# STM32.net
KiCad netlist of a schematic drawn in Altium Designer
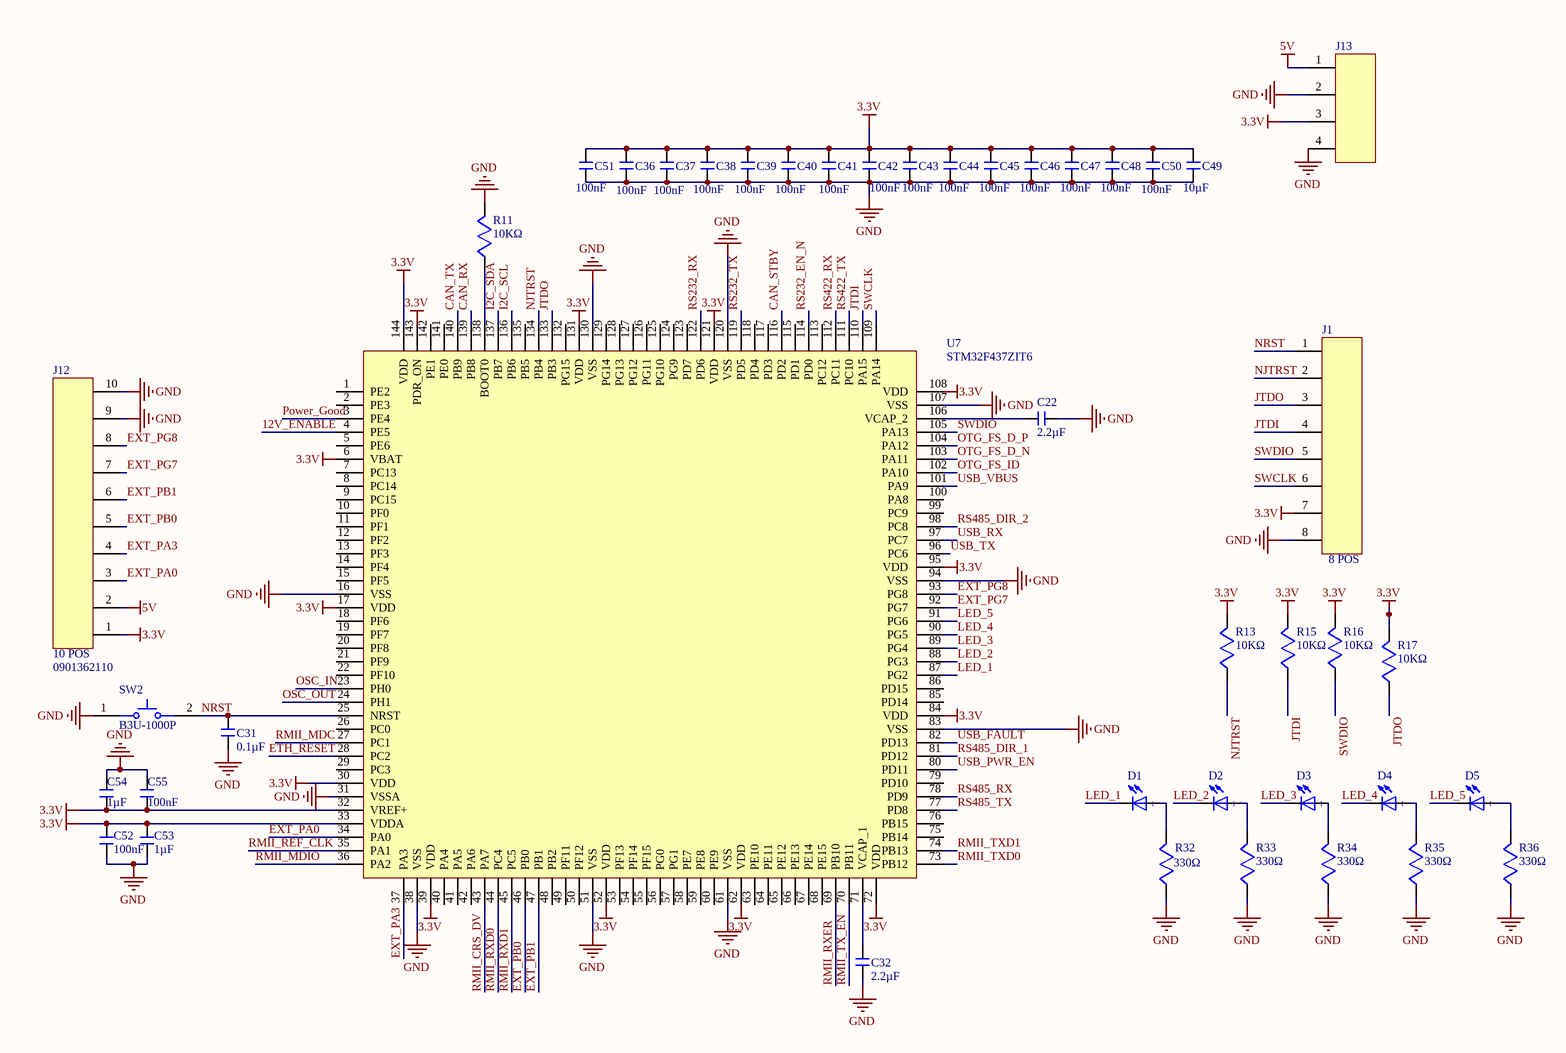
[diagram p0: STM32.SchDoc]

(export (version "E")
  (design (tool "Eeschema 10.0.6"))
  (components
    (comp (ref "C22")
      (value "2.2µF")
      (footprint "402 capacitor - duplicate")
      (description "CAP SMD 402")
      (fields (field (name "MPN") "C1005X5R1V225K050BC") (field (name "Comment") "0402 capacitor"))
      (libsource (lib "Schlib1") (part "CAP SMD 402"))
    )
    (comp (ref "C31")
      (value "0.1µF")
      (footprint "402 capacitor - duplicate")
      (description "CAP SMD 402")
      (fields (field (name "MPN") "CL05A104KA5NNNC") (field (name "Comment") "0402 capacitor"))
      (libsource (lib "Schlib1") (part "CAP SMD 402"))
    )
    (comp (ref "C32")
      (value "2.2µF")
      (footprint "402 capacitor - duplicate")
      (description "CAP SMD 402")
      (fields (field (name "MPN") "C1005X5R1V225K050BC") (field (name "Comment") "0402 capacitor"))
      (libsource (lib "Schlib1") (part "CAP SMD 402"))
    )
    (comp (ref "C36")
      (value "100nF")
      (footprint "402 capacitor - duplicate")
      (description "CAP SMD 402")
      (fields (field (name "MPN") "CL05A104KA5NNNC") (field (name "Comment") "0402 capacitor"))
      (libsource (lib "Schlib1") (part "CAP SMD 402"))
    )
    (comp (ref "C37")
      (value "100nF")
      (footprint "402 capacitor - duplicate")
      (description "CAP SMD 402")
      (fields (field (name "MPN") "CL05A104KA5NNNC") (field (name "Comment") "0402 capacitor"))
      (libsource (lib "Schlib1") (part "CAP SMD 402"))
    )
    (comp (ref "C38")
      (value "100nF")
      (footprint "402 capacitor - duplicate")
      (description "CAP SMD 402")
      (fields (field (name "MPN") "CL05A104KA5NNNC") (field (name "Comment") "0402 capacitor"))
      (libsource (lib "Schlib1") (part "CAP SMD 402"))
    )
    (comp (ref "C39")
      (value "100nF")
      (footprint "402 capacitor - duplicate")
      (description "CAP SMD 402")
      (fields (field (name "MPN") "CL05A104KA5NNNC") (field (name "Comment") "0402 capacitor"))
      (libsource (lib "Schlib1") (part "CAP SMD 402"))
    )
    (comp (ref "C40")
      (value "100nF")
      (footprint "402 capacitor - duplicate")
      (description "CAP SMD 402")
      (fields (field (name "MPN") "CL05A104KA5NNNC") (field (name "Comment") "0402 capacitor"))
      (libsource (lib "Schlib1") (part "CAP SMD 402"))
    )
    (comp (ref "C41")
      (value "100nF")
      (footprint "402 capacitor - duplicate")
      (description "CAP SMD 402")
      (fields (field (name "MPN") "CL05A104KA5NNNC") (field (name "Comment") "0402 capacitor"))
      (libsource (lib "Schlib1") (part "CAP SMD 402"))
    )
    (comp (ref "C42")
      (value "100nF")
      (footprint "402 capacitor - duplicate")
      (description "CAP SMD 402")
      (fields (field (name "MPN") "CL05A104KA5NNNC") (field (name "Comment") "0402 capacitor"))
      (libsource (lib "Schlib1") (part "CAP SMD 402"))
    )
    (comp (ref "C43")
      (value "100nF")
      (footprint "402 capacitor - duplicate")
      (description "CAP SMD 402")
      (fields (field (name "MPN") "CL05A104KA5NNNC") (field (name "Comment") "0402 capacitor"))
      (libsource (lib "Schlib1") (part "CAP SMD 402"))
    )
    (comp (ref "C44")
      (value "100nF")
      (footprint "402 capacitor - duplicate")
      (description "CAP SMD 402")
      (fields (field (name "MPN") "CL05A104KA5NNNC") (field (name "Comment") "0402 capacitor"))
      (libsource (lib "Schlib1") (part "CAP SMD 402"))
    )
    (comp (ref "C45")
      (value "100nF")
      (footprint "402 capacitor - duplicate")
      (description "CAP SMD 402")
      (fields (field (name "MPN") "CL05A104KA5NNNC") (field (name "Comment") "0402 capacitor"))
      (libsource (lib "Schlib1") (part "CAP SMD 402"))
    )
    (comp (ref "C46")
      (value "100nF")
      (footprint "402 capacitor - duplicate")
      (description "CAP SMD 402")
      (fields (field (name "MPN") "CL05A104KA5NNNC") (field (name "Comment") "0402 capacitor"))
      (libsource (lib "Schlib1") (part "CAP SMD 402"))
    )
    (comp (ref "C47")
      (value "100nF")
      (footprint "402 capacitor - duplicate")
      (description "CAP SMD 402")
      (fields (field (name "MPN") "CL05A104KA5NNNC") (field (name "Comment") "0402 capacitor"))
      (libsource (lib "Schlib1") (part "CAP SMD 402"))
    )
    (comp (ref "C48")
      (value "100nF")
      (footprint "402 capacitor - duplicate")
      (description "CAP SMD 402")
      (fields (field (name "MPN") "CL05A104KA5NNNC") (field (name "Comment") "0402 capacitor"))
      (libsource (lib "Schlib1") (part "CAP SMD 402"))
    )
    (comp (ref "C49")
      (value "10µF")
      (footprint "603 CAPACITOR")
      (description "CAP SMD 0603")
      (fields (field (name "MPN") "GRM188R61E106MA73D") (field (name "Comment") "0603 CAPACİTOR"))
      (libsource (lib "Schlib1") (part "CAP SMD 0603"))
    )
    (comp (ref "C50")
      (value "100nF")
      (footprint "402 capacitor - duplicate")
      (description "CAP SMD 402")
      (fields (field (name "MPN") "CL05A104KA5NNNC") (field (name "Comment") "0402 capacitor"))
      (libsource (lib "Schlib1") (part "CAP SMD 402"))
    )
    (comp (ref "C51")
      (value "100nF")
      (footprint "402 capacitor - duplicate")
      (description "CAP SMD 402")
      (fields (field (name "MPN") "CL05A104KA5NNNC") (field (name "Comment") "0402 capacitor"))
      (libsource (lib "Schlib1") (part "CAP SMD 402"))
    )
    (comp (ref "C52")
      (value "100nF")
      (footprint "402 capacitor - duplicate")
      (description "CAP SMD 402")
      (fields (field (name "MPN") "CL05A104KA5NNNC") (field (name "Comment") "0402 capacitor"))
      (libsource (lib "Schlib1") (part "CAP SMD 402"))
    )
    (comp (ref "C53")
      (value "1µF")
      (footprint "402 capacitor - duplicate")
      (description "CAP SMD 402")
      (fields (field (name "MPN") "GRM155R6YA105KE11D") (field (name "Comment") "0402 capacitor"))
      (libsource (lib "Schlib1") (part "CAP SMD 402"))
    )
    (comp (ref "C54")
      (value "1µF")
      (footprint "402 capacitor - duplicate")
      (description "CAP SMD 402")
      (fields (field (name "MPN") "GRM155R6YA105KE11D") (field (name "Comment") "0402 capacitor"))
      (libsource (lib "Schlib1") (part "CAP SMD 402"))
    )
    (comp (ref "C55")
      (value "100nF")
      (footprint "402 capacitor - duplicate")
      (description "CAP SMD 402")
      (fields (field (name "MPN") "CL05A104KA5NNNC") (field (name "Comment") "0402 capacitor"))
      (libsource (lib "Schlib1") (part "CAP SMD 402"))
    )
    (comp (ref "D1")
      (value "150060RS75000")
      (footprint "150080GS75000")
      (description "LED RED CLEAR 0603 SMD")
      (libsource (lib "Schlib1") (part "150060RS75000"))
    )
    (comp (ref "D2")
      (value "150060RS75000")
      (footprint "150080GS75000")
      (description "LED RED CLEAR 0603 SMD")
      (libsource (lib "Schlib1") (part "150060RS75000"))
    )
    (comp (ref "D3")
      (value "150060RS75000")
      (footprint "150080GS75000")
      (description "LED RED CLEAR 0603 SMD")
      (libsource (lib "Schlib1") (part "150060RS75000"))
    )
    (comp (ref "D4")
      (value "150060RS75000")
      (footprint "150080GS75000")
      (description "LED RED CLEAR 0603 SMD")
      (libsource (lib "Schlib1") (part "150060RS75000"))
    )
    (comp (ref "D5")
      (value "150060RS75000")
      (footprint "150080GS75000")
      (description "LED RED CLEAR 0603 SMD")
      (libsource (lib "Schlib1") (part "150060RS75000"))
    )
    (comp (ref "J1")
      (value "8 POS")
      (footprint "0901362108")
      (description "CONN HEADER R/A 8POS 2.54MM")
      (fields (field (name "MPN") "0901362108"))
      (libsource (lib "Schlib1") (part "0901362108"))
    )
    (comp (ref "J12")
      (value "10 POS")
      (footprint "0901362110")
      (description "CONN HEADER R/A 10POS 2.54MM")
      (fields (field (name "MPN") "0901362110"))
      (libsource (lib "Schlib1") (part "0901362110"))
    )
    (comp (ref "J13")
      (value "61300411821")
      (footprint "61300411821")
      (description "WR-PHD 2.54 MM SOCKET HEADER 4 P")
      (libsource (lib "Schlib1") (part "61300411821"))
    )
    (comp (ref "R11")
      (value "10KΩ")
      (footprint "402 RESISTOR")
      (description "RES SMD 0402")
      (fields (field (name "MPN") "RNCF0402BTE10K0") (field (name "Comment") "0402. RESİSTOR"))
      (libsource (lib "Schlib1") (part "RES SMD 0402"))
    )
    (comp (ref "R13")
      (value "10KΩ")
      (footprint "402 RESISTOR")
      (description "RES SMD 0402")
      (fields (field (name "MPN") "RNCF0402BTE10K0") (field (name "Comment") "0402. RESİSTOR"))
      (libsource (lib "Schlib1") (part "RES SMD 0402"))
    )
    (comp (ref "R15")
      (value "10KΩ")
      (footprint "402 RESISTOR")
      (description "RES SMD 0402")
      (fields (field (name "MPN") "RNCF0402BTE10K0") (field (name "Comment") "0402. RESİSTOR"))
      (libsource (lib "Schlib1") (part "RES SMD 0402"))
    )
    (comp (ref "R16")
      (value "10KΩ")
      (footprint "402 RESISTOR")
      (description "RES SMD 0402")
      (fields (field (name "MPN") "RNCF0402BTE10K0") (field (name "Comment") "0402. RESİSTOR"))
      (libsource (lib "Schlib1") (part "RES SMD 0402"))
    )
    (comp (ref "R17")
      (value "10KΩ")
      (footprint "402 RESISTOR")
      (description "RES SMD 0402")
      (fields (field (name "MPN") "RNCF0402BTE10K0") (field (name "Comment") "0402. RESİSTOR"))
      (libsource (lib "Schlib1") (part "RES SMD 0402"))
    )
    (comp (ref "R32")
      (value "330Ω")
      (footprint "402 RESISTOR")
      (description "RES SMD 0402")
      (fields (field (name "MPN") "RC0402FR-13300RL") (field (name "Comment") "0402. RESİSTOR"))
      (libsource (lib "Schlib1") (part "RES SMD 0402"))
    )
    (comp (ref "R33")
      (value "330Ω")
      (footprint "402 RESISTOR")
      (description "RES SMD 0402")
      (fields (field (name "MPN") "RC0402FR-13300RL") (field (name "Comment") "0402. RESİSTOR"))
      (libsource (lib "Schlib1") (part "RES SMD 0402"))
    )
    (comp (ref "R34")
      (value "330Ω")
      (footprint "402 RESISTOR")
      (description "RES SMD 0402")
      (fields (field (name "MPN") "RC0402FR-13300RL") (field (name "Comment") "0402. RESİSTOR"))
      (libsource (lib "Schlib1") (part "RES SMD 0402"))
    )
    (comp (ref "R35")
      (value "330Ω")
      (footprint "402 RESISTOR")
      (description "RES SMD 0402")
      (fields (field (name "MPN") "RC0402FR-13300RL") (field (name "Comment") "0402. RESİSTOR"))
      (libsource (lib "Schlib1") (part "RES SMD 0402"))
    )
    (comp (ref "R36")
      (value "330Ω")
      (footprint "402 RESISTOR")
      (description "RES SMD 0402")
      (fields (field (name "MPN") "RC0402FR-13300RL") (field (name "Comment") "0402. RESİSTOR"))
      (libsource (lib "Schlib1") (part "RES SMD 0402"))
    )
    (comp (ref "SW2")
      (value "B3U-1000P")
      (footprint "OMRON-B3U-1000_V")
      (description "Tactile Switch, SPST-NO, 0.05 A, 12 V, -25 to 70 degC, 2-Pin SMD, RoHS, Tape and Reel")
      (libsource (lib "Veysel Can Tosun") (part "SW-SPST-NO-2"))
    )
    (comp (ref "U7")
      (value "STM32F437ZIT6")
      (footprint "STM32F437ZIT6")
      (fields (field (name "MANUFACTURER") "STMicroelectronics"))
      (libsource (lib "Schlib1") (part "STM32F437ZIT6"))
    )
  )
  (nets
    (net (code "1") (name "/12V_ENABLE") (class "Default")
      (node (ref "U7") (pin "4") (pinfunction "PE5_4") (pintype "passive"))
    )
    (net (code "2") (name "/CAN_RX") (class "Default")
      (node (ref "U7") (pin "139") (pinfunction "PB8_139") (pintype "passive"))
    )
    (net (code "3") (name "/CAN_STBY") (class "Default")
      (node (ref "U7") (pin "116") (pinfunction "PD2_116") (pintype "passive"))
    )
    (net (code "4") (name "/CAN_TX") (class "Default")
      (node (ref "U7") (pin "140") (pinfunction "PB9_140") (pintype "passive"))
    )
    (net (code "5") (name "/ETH_RESET") (class "Default")
      (node (ref "U7") (pin "28") (pinfunction "PC2_28") (pintype "passive"))
    )
    (net (code "6") (name "/EXT_PA0") (class "Default")
      (node (ref "J12") (pin "3") (pintype "passive"))
      (node (ref "U7") (pin "34") (pinfunction "PA0_34") (pintype "passive"))
    )
    (net (code "7") (name "/EXT_PA3") (class "Default")
      (node (ref "J12") (pin "4") (pintype "passive"))
      (node (ref "U7") (pin "37") (pinfunction "PA3_37") (pintype "passive"))
    )
    (net (code "8") (name "/EXT_PB0") (class "Default")
      (node (ref "J12") (pin "5") (pintype "passive"))
      (node (ref "U7") (pin "46") (pinfunction "PB0_46") (pintype "passive"))
    )
    (net (code "9") (name "/EXT_PB1") (class "Default")
      (node (ref "J12") (pin "6") (pintype "passive"))
      (node (ref "U7") (pin "47") (pinfunction "PB1_47") (pintype "passive"))
    )
    (net (code "10") (name "/EXT_PG7") (class "Default")
      (node (ref "J12") (pin "7") (pintype "passive"))
      (node (ref "U7") (pin "92") (pinfunction "PG7_92") (pintype "passive"))
    )
    (net (code "11") (name "/EXT_PG8") (class "Default")
      (node (ref "J12") (pin "8") (pintype "passive"))
      (node (ref "U7") (pin "93") (pinfunction "PG8_93") (pintype "passive"))
    )
    (net (code "12") (name "/I2C_SCL") (class "Default")
      (node (ref "U7") (pin "136") (pinfunction "PB6_136") (pintype "passive"))
    )
    (net (code "13") (name "/I2C_SDA") (class "Default")
      (node (ref "U7") (pin "137") (pinfunction "PB7_137") (pintype "passive"))
    )
    (net (code "14") (name "/JTDI") (class "Default")
      (node (ref "J1") (pin "4") (pintype "passive"))
      (node (ref "R15") (pin "1") (pintype "passive"))
      (node (ref "U7") (pin "110") (pinfunction "PA15_110") (pintype "passive"))
    )
    (net (code "15") (name "/JTDO") (class "Default")
      (node (ref "J1") (pin "3") (pintype "passive"))
      (node (ref "R17") (pin "1") (pintype "passive"))
      (node (ref "U7") (pin "133") (pinfunction "PB3_133") (pintype "passive"))
    )
    (net (code "16") (name "/LED_1") (class "Default")
      (node (ref "D1") (pin "1") (pinfunction "NEG_1") (pintype "passive"))
      (node (ref "U7") (pin "87") (pinfunction "PG2_87") (pintype "passive"))
    )
    (net (code "17") (name "/LED_2") (class "Default")
      (node (ref "D2") (pin "1") (pinfunction "NEG_1") (pintype "passive"))
      (node (ref "U7") (pin "88") (pinfunction "PG3_88") (pintype "passive"))
    )
    (net (code "18") (name "/LED_3") (class "Default")
      (node (ref "D3") (pin "1") (pinfunction "NEG_1") (pintype "passive"))
      (node (ref "U7") (pin "89") (pinfunction "PG4_89") (pintype "passive"))
    )
    (net (code "19") (name "/LED_4") (class "Default")
      (node (ref "D4") (pin "1") (pinfunction "NEG_1") (pintype "passive"))
      (node (ref "U7") (pin "90") (pinfunction "PG5_90") (pintype "passive"))
    )
    (net (code "20") (name "/LED_5") (class "Default")
      (node (ref "D5") (pin "1") (pinfunction "NEG_1") (pintype "passive"))
      (node (ref "U7") (pin "91") (pinfunction "PG6_91") (pintype "passive"))
    )
    (net (code "21") (name "/NJTRST") (class "Default")
      (node (ref "J1") (pin "2") (pintype "passive"))
      (node (ref "R13") (pin "1") (pintype "passive"))
      (node (ref "U7") (pin "134") (pinfunction "PB4_134") (pintype "passive"))
    )
    (net (code "22") (name "/NRST") (class "Default")
      (node (ref "C31") (pin "2") (pintype "passive"))
      (node (ref "J1") (pin "1") (pintype "passive"))
      (node (ref "SW2") (pin "2") (pinfunction "2_2") (pintype "passive"))
      (node (ref "U7") (pin "25") (pinfunction "NRST_25") (pintype "passive"))
    )
    (net (code "23") (name "/OSC_IN") (class "Default")
      (node (ref "U7") (pin "23") (pinfunction "PH0_23") (pintype "passive"))
    )
    (net (code "24") (name "/OSC_OUT") (class "Default")
      (node (ref "U7") (pin "24") (pinfunction "PH1_24") (pintype "passive"))
    )
    (net (code "25") (name "/OTG_FS_D_N") (class "Default")
      (node (ref "U7") (pin "103") (pinfunction "PA11_103") (pintype "passive"))
    )
    (net (code "26") (name "/OTG_FS_D_P") (class "Default")
      (node (ref "U7") (pin "104") (pinfunction "PA12_104") (pintype "passive"))
    )
    (net (code "27") (name "/OTG_FS_ID") (class "Default")
      (node (ref "U7") (pin "102") (pinfunction "PA10_102") (pintype "passive"))
    )
    (net (code "28") (name "/Power_Good") (class "Default")
      (node (ref "U7") (pin "3") (pinfunction "PE4_3") (pintype "passive"))
    )
    (net (code "29") (name "/RMII_CRS_DV") (class "Default")
      (node (ref "U7") (pin "43") (pinfunction "PA7_43") (pintype "passive"))
    )
    (net (code "30") (name "/RMII_MDC") (class "Default")
      (node (ref "U7") (pin "27") (pinfunction "PC1_27") (pintype "passive"))
    )
    (net (code "31") (name "/RMII_MDIO") (class "Default")
      (node (ref "U7") (pin "36") (pinfunction "PA2_36") (pintype "passive"))
    )
    (net (code "32") (name "/RMII_REF_CLK") (class "Default")
      (node (ref "U7") (pin "35") (pinfunction "PA1_35") (pintype "passive"))
    )
    (net (code "33") (name "/RMII_RXD0") (class "Default")
      (node (ref "U7") (pin "44") (pinfunction "PC4_44") (pintype "passive"))
    )
    (net (code "34") (name "/RMII_RXD1") (class "Default")
      (node (ref "U7") (pin "45") (pinfunction "PC5_45") (pintype "passive"))
    )
    (net (code "35") (name "/RMII_RXER") (class "Default")
      (node (ref "U7") (pin "69") (pinfunction "PB10_69") (pintype "passive"))
    )
    (net (code "36") (name "/RMII_TXD0") (class "Default")
      (node (ref "U7") (pin "73") (pinfunction "PB12_73") (pintype "passive"))
    )
    (net (code "37") (name "/RMII_TXD1") (class "Default")
      (node (ref "U7") (pin "74") (pinfunction "PB13_74") (pintype "passive"))
    )
    (net (code "38") (name "/RMII_TX_EN") (class "Default")
      (node (ref "U7") (pin "70") (pinfunction "PB11_70") (pintype "passive"))
    )
    (net (code "39") (name "/RS232_EN_N") (class "Default")
      (node (ref "U7") (pin "114") (pinfunction "PD0_114") (pintype "passive"))
    )
    (net (code "40") (name "/RS232_RX") (class "Default")
      (node (ref "U7") (pin "122") (pinfunction "PD6_122") (pintype "passive"))
    )
    (net (code "41") (name "/RS232_TX") (class "Default")
      (node (ref "U7") (pin "119") (pinfunction "PD5_119") (pintype "passive"))
    )
    (net (code "42") (name "/RS422_RX") (class "Default")
      (node (ref "U7") (pin "112") (pinfunction "PC11_112") (pintype "passive"))
    )
    (net (code "43") (name "/RS422_TX") (class "Default")
      (node (ref "U7") (pin "111") (pinfunction "PC10_111") (pintype "passive"))
    )
    (net (code "44") (name "/RS485_DIR_1") (class "Default")
      (node (ref "U7") (pin "81") (pinfunction "PD12_81") (pintype "passive"))
    )
    (net (code "45") (name "/RS485_DIR_2") (class "Default")
      (node (ref "U7") (pin "98") (pinfunction "PC8_98") (pintype "passive"))
    )
    (net (code "46") (name "/RS485_RX") (class "Default")
      (node (ref "U7") (pin "78") (pinfunction "PD9_78") (pintype "passive"))
    )
    (net (code "47") (name "/RS485_TX") (class "Default")
      (node (ref "U7") (pin "77") (pinfunction "PD8_77") (pintype "passive"))
    )
    (net (code "48") (name "/SWCLK") (class "Default")
      (node (ref "J1") (pin "6") (pintype "passive"))
      (node (ref "U7") (pin "109") (pinfunction "PA14_109") (pintype "passive"))
    )
    (net (code "49") (name "/SWDIO") (class "Default")
      (node (ref "J1") (pin "5") (pintype "passive"))
      (node (ref "R16") (pin "1") (pintype "passive"))
      (node (ref "U7") (pin "105") (pinfunction "PA13_105") (pintype "passive"))
    )
    (net (code "50") (name "/USB_FAULT") (class "Default")
      (node (ref "U7") (pin "82") (pinfunction "PD13_82") (pintype "passive"))
    )
    (net (code "51") (name "/USB_PWR_EN") (class "Default")
      (node (ref "U7") (pin "80") (pinfunction "PD11_80") (pintype "passive"))
    )
    (net (code "52") (name "/USB_RX") (class "Default")
      (node (ref "U7") (pin "97") (pinfunction "PC7_97") (pintype "passive"))
    )
    (net (code "53") (name "/USB_TX") (class "Default")
      (node (ref "U7") (pin "96") (pinfunction "PC6_96") (pintype "passive"))
    )
    (net (code "54") (name "/USB_VBUS") (class "Default")
      (node (ref "U7") (pin "101") (pinfunction "PA9_101") (pintype "passive"))
    )
    (net (code "55") (name "3.3V") (class "Default")
      (node (ref "C36") (pin "1") (pintype "passive"))
      (node (ref "C37") (pin "1") (pintype "passive"))
      (node (ref "C38") (pin "1") (pintype "passive"))
      (node (ref "C39") (pin "1") (pintype "passive"))
      (node (ref "C40") (pin "1") (pintype "passive"))
      (node (ref "C41") (pin "1") (pintype "passive"))
      (node (ref "C42") (pin "1") (pintype "passive"))
      (node (ref "C43") (pin "1") (pintype "passive"))
      (node (ref "C44") (pin "1") (pintype "passive"))
      (node (ref "C45") (pin "1") (pintype "passive"))
      (node (ref "C46") (pin "1") (pintype "passive"))
      (node (ref "C47") (pin "1") (pintype "passive"))
      (node (ref "C48") (pin "1") (pintype "passive"))
      (node (ref "C49") (pin "2") (pintype "passive"))
      (node (ref "C50") (pin "1") (pintype "passive"))
      (node (ref "C51") (pin "1") (pintype "passive"))
      (node (ref "C52") (pin "2") (pintype "passive"))
      (node (ref "C53") (pin "2") (pintype "passive"))
      (node (ref "C54") (pin "2") (pintype "passive"))
      (node (ref "C55") (pin "2") (pintype "passive"))
      (node (ref "J1") (pin "7") (pintype "passive"))
      (node (ref "J12") (pin "1") (pintype "passive"))
      (node (ref "J13") (pin "3") (pintype "passive"))
      (node (ref "R13") (pin "2") (pintype "passive"))
      (node (ref "R15") (pin "2") (pintype "passive"))
      (node (ref "R16") (pin "2") (pintype "passive"))
      (node (ref "R17") (pin "2") (pintype "passive"))
      (node (ref "U7") (pin "108") (pinfunction "VDD_108") (pintype "passive"))
      (node (ref "U7") (pin "121") (pinfunction "VDD_121") (pintype "passive"))
      (node (ref "U7") (pin "131") (pinfunction "VDD_131") (pintype "passive"))
      (node (ref "U7") (pin "143") (pinfunction "PDR_ON_143") (pintype "passive"))
      (node (ref "U7") (pin "144") (pinfunction "VDD_144") (pintype "passive"))
      (node (ref "U7") (pin "17") (pinfunction "VDD_17") (pintype "passive"))
      (node (ref "U7") (pin "30") (pinfunction "VDD_30") (pintype "passive"))
      (node (ref "U7") (pin "32") (pinfunction "VREF+_32") (pintype "passive"))
      (node (ref "U7") (pin "33") (pinfunction "VDDA_33") (pintype "passive"))
      (node (ref "U7") (pin "39") (pinfunction "VDD_39") (pintype "passive"))
      (node (ref "U7") (pin "52") (pinfunction "VDD_52") (pintype "passive"))
      (node (ref "U7") (pin "6") (pinfunction "VBAT_6") (pintype "passive"))
      (node (ref "U7") (pin "62") (pinfunction "VDD_62") (pintype "passive"))
      (node (ref "U7") (pin "72") (pinfunction "VDD_72") (pintype "passive"))
      (node (ref "U7") (pin "84") (pinfunction "VDD_84") (pintype "passive"))
      (node (ref "U7") (pin "95") (pinfunction "VDD_95") (pintype "passive"))
    )
    (net (code "56") (name "5V") (class "Default")
      (node (ref "J12") (pin "2") (pintype "passive"))
      (node (ref "J13") (pin "1") (pintype "passive"))
    )
    (net (code "57") (name "GND") (class "Default")
      (node (ref "C22") (pin "2") (pintype "passive"))
      (node (ref "C31") (pin "1") (pintype "passive"))
      (node (ref "C32") (pin "1") (pintype "passive"))
      (node (ref "C36") (pin "2") (pintype "passive"))
      (node (ref "C37") (pin "2") (pintype "passive"))
      (node (ref "C38") (pin "2") (pintype "passive"))
      (node (ref "C39") (pin "2") (pintype "passive"))
      (node (ref "C40") (pin "2") (pintype "passive"))
      (node (ref "C41") (pin "2") (pintype "passive"))
      (node (ref "C42") (pin "2") (pintype "passive"))
      (node (ref "C43") (pin "2") (pintype "passive"))
      (node (ref "C44") (pin "2") (pintype "passive"))
      (node (ref "C45") (pin "2") (pintype "passive"))
      (node (ref "C46") (pin "2") (pintype "passive"))
      (node (ref "C47") (pin "2") (pintype "passive"))
      (node (ref "C48") (pin "2") (pintype "passive"))
      (node (ref "C49") (pin "1") (pintype "passive"))
      (node (ref "C50") (pin "2") (pintype "passive"))
      (node (ref "C51") (pin "2") (pintype "passive"))
      (node (ref "C52") (pin "1") (pintype "passive"))
      (node (ref "C53") (pin "1") (pintype "passive"))
      (node (ref "C54") (pin "1") (pintype "passive"))
      (node (ref "C55") (pin "1") (pintype "passive"))
      (node (ref "J1") (pin "8") (pintype "passive"))
      (node (ref "J12") (pin "10") (pintype "passive"))
      (node (ref "J12") (pin "9") (pintype "passive"))
      (node (ref "J13") (pin "2") (pintype "passive"))
      (node (ref "J13") (pin "4") (pintype "passive"))
      (node (ref "R11") (pin "2") (pintype "passive"))
      (node (ref "R32") (pin "1") (pintype "passive"))
      (node (ref "R33") (pin "1") (pintype "passive"))
      (node (ref "R34") (pin "1") (pintype "passive"))
      (node (ref "R35") (pin "1") (pintype "passive"))
      (node (ref "R36") (pin "1") (pintype "passive"))
      (node (ref "SW2") (pin "1") (pinfunction "1_1") (pintype "passive"))
      (node (ref "U7") (pin "107") (pinfunction "VSS_107") (pintype "passive"))
      (node (ref "U7") (pin "120") (pinfunction "VSS_120") (pintype "passive"))
      (node (ref "U7") (pin "130") (pinfunction "VSS_130") (pintype "passive"))
      (node (ref "U7") (pin "16") (pinfunction "VSS_16") (pintype "passive"))
      (node (ref "U7") (pin "31") (pinfunction "VSSA_31") (pintype "passive"))
      (node (ref "U7") (pin "38") (pinfunction "VSS_38") (pintype "passive"))
      (node (ref "U7") (pin "51") (pinfunction "VSS_51") (pintype "passive"))
      (node (ref "U7") (pin "61") (pinfunction "VSS_61") (pintype "passive"))
      (node (ref "U7") (pin "83") (pinfunction "VSS_83") (pintype "passive"))
      (node (ref "U7") (pin "94") (pinfunction "VSS_94") (pintype "passive"))
    )
    (net (code "58") (name "Net-(D1-POS)") (class "Default")
      (node (ref "D1") (pin "2") (pinfunction "POS_2") (pintype "passive"))
      (node (ref "R32") (pin "2") (pintype "passive"))
    )
    (net (code "59") (name "Net-(D2-POS)") (class "Default")
      (node (ref "D2") (pin "2") (pinfunction "POS_2") (pintype "passive"))
      (node (ref "R33") (pin "2") (pintype "passive"))
    )
    (net (code "60") (name "Net-(D3-POS)") (class "Default")
      (node (ref "D3") (pin "2") (pinfunction "POS_2") (pintype "passive"))
      (node (ref "R34") (pin "2") (pintype "passive"))
    )
    (net (code "61") (name "Net-(D4-POS)") (class "Default")
      (node (ref "D4") (pin "2") (pinfunction "POS_2") (pintype "passive"))
      (node (ref "R35") (pin "2") (pintype "passive"))
    )
    (net (code "62") (name "Net-(D5-POS)") (class "Default")
      (node (ref "D5") (pin "2") (pinfunction "POS_2") (pintype "passive"))
      (node (ref "R36") (pin "2") (pintype "passive"))
    )
    (net (code "63") (name "Net-(U7-BOOT0)") (class "Default")
      (node (ref "R11") (pin "1") (pintype "passive"))
      (node (ref "U7") (pin "138") (pinfunction "BOOT0_138") (pintype "passive"))
    )
    (net (code "64") (name "Net-(U7-VCAP_1)") (class "Default")
      (node (ref "C32") (pin "2") (pintype "passive"))
      (node (ref "U7") (pin "71") (pinfunction "VCAP_1_71") (pintype "passive"))
    )
    (net (code "65") (name "Net-(U7-VCAP_2)") (class "Default")
      (node (ref "C22") (pin "1") (pintype "passive"))
      (node (ref "U7") (pin "106") (pinfunction "VCAP_2_106") (pintype "passive"))
    )
    (net (code "66") (name "unconnected-(U7-PA4-Pad40)") (class "Default")
      (node (ref "U7") (pin "40") (pinfunction "PA4_40") (pintype "passive"))
    )
    (net (code "67") (name "unconnected-(U7-PA5-Pad41)") (class "Default")
      (node (ref "U7") (pin "41") (pinfunction "PA5_41") (pintype "passive"))
    )
    (net (code "68") (name "unconnected-(U7-PA6-Pad42)") (class "Default")
      (node (ref "U7") (pin "42") (pinfunction "PA6_42") (pintype "passive"))
    )
    (net (code "69") (name "unconnected-(U7-PA8-Pad100)") (class "Default")
      (node (ref "U7") (pin "100") (pinfunction "PA8_100") (pintype "passive"))
    )
    (net (code "70") (name "unconnected-(U7-PB2-Pad48)") (class "Default")
      (node (ref "U7") (pin "48") (pinfunction "PB2_48") (pintype "passive"))
    )
    (net (code "71") (name "unconnected-(U7-PB5-Pad135)") (class "Default")
      (node (ref "U7") (pin "135") (pinfunction "PB5_135") (pintype "passive"))
    )
    (net (code "72") (name "unconnected-(U7-PB14-Pad75)") (class "Default")
      (node (ref "U7") (pin "75") (pinfunction "PB14_75") (pintype "passive"))
    )
    (net (code "73") (name "unconnected-(U7-PB15-Pad76)") (class "Default")
      (node (ref "U7") (pin "76") (pinfunction "PB15_76") (pintype "passive"))
    )
    (net (code "74") (name "unconnected-(U7-PC0-Pad26)") (class "Default")
      (node (ref "U7") (pin "26") (pinfunction "PC0_26") (pintype "passive"))
    )
    (net (code "75") (name "unconnected-(U7-PC3-Pad29)") (class "Default")
      (node (ref "U7") (pin "29") (pinfunction "PC3_29") (pintype "passive"))
    )
    (net (code "76") (name "unconnected-(U7-PC9-Pad99)") (class "Default")
      (node (ref "U7") (pin "99") (pinfunction "PC9_99") (pintype "passive"))
    )
    (net (code "77") (name "unconnected-(U7-PC12-Pad113)") (class "Default")
      (node (ref "U7") (pin "113") (pinfunction "PC12_113") (pintype "passive"))
    )
    (net (code "78") (name "unconnected-(U7-PC13-Pad7)") (class "Default")
      (node (ref "U7") (pin "7") (pinfunction "PC13_7") (pintype "passive"))
    )
    (net (code "79") (name "unconnected-(U7-PC14-Pad8)") (class "Default")
      (node (ref "U7") (pin "8") (pinfunction "PC14_8") (pintype "passive"))
    )
    (net (code "80") (name "unconnected-(U7-PC15-Pad9)") (class "Default")
      (node (ref "U7") (pin "9") (pinfunction "PC15_9") (pintype "passive"))
    )
    (net (code "81") (name "unconnected-(U7-PD1-Pad115)") (class "Default")
      (node (ref "U7") (pin "115") (pinfunction "PD1_115") (pintype "passive"))
    )
    (net (code "82") (name "unconnected-(U7-PD3-Pad117)") (class "Default")
      (node (ref "U7") (pin "117") (pinfunction "PD3_117") (pintype "passive"))
    )
    (net (code "83") (name "unconnected-(U7-PD4-Pad118)") (class "Default")
      (node (ref "U7") (pin "118") (pinfunction "PD4_118") (pintype "passive"))
    )
    (net (code "84") (name "unconnected-(U7-PD7-Pad123)") (class "Default")
      (node (ref "U7") (pin "123") (pinfunction "PD7_123") (pintype "passive"))
    )
    (net (code "85") (name "unconnected-(U7-PD10-Pad79)") (class "Default")
      (node (ref "U7") (pin "79") (pinfunction "PD10_79") (pintype "passive"))
    )
    (net (code "86") (name "unconnected-(U7-PD14-Pad85)") (class "Default")
      (node (ref "U7") (pin "85") (pinfunction "PD14_85") (pintype "passive"))
    )
    (net (code "87") (name "unconnected-(U7-PD15-Pad86)") (class "Default")
      (node (ref "U7") (pin "86") (pinfunction "PD15_86") (pintype "passive"))
    )
    (net (code "88") (name "unconnected-(U7-PE0-Pad141)") (class "Default")
      (node (ref "U7") (pin "141") (pinfunction "PE0_141") (pintype "passive"))
    )
    (net (code "89") (name "unconnected-(U7-PE1-Pad142)") (class "Default")
      (node (ref "U7") (pin "142") (pinfunction "PE1_142") (pintype "passive"))
    )
    (net (code "90") (name "unconnected-(U7-PE2-Pad1)") (class "Default")
      (node (ref "U7") (pin "1") (pinfunction "PE2_1") (pintype "passive"))
    )
    (net (code "91") (name "unconnected-(U7-PE3-Pad2)") (class "Default")
      (node (ref "U7") (pin "2") (pinfunction "PE3_2") (pintype "passive"))
    )
    (net (code "92") (name "unconnected-(U7-PE6-Pad5)") (class "Default")
      (node (ref "U7") (pin "5") (pinfunction "PE6_5") (pintype "passive"))
    )
    (net (code "93") (name "unconnected-(U7-PE7-Pad58)") (class "Default")
      (node (ref "U7") (pin "58") (pinfunction "PE7_58") (pintype "passive"))
    )
    (net (code "94") (name "unconnected-(U7-PE8-Pad59)") (class "Default")
      (node (ref "U7") (pin "59") (pinfunction "PE8_59") (pintype "passive"))
    )
    (net (code "95") (name "unconnected-(U7-PE9-Pad60)") (class "Default")
      (node (ref "U7") (pin "60") (pinfunction "PE9_60") (pintype "passive"))
    )
    (net (code "96") (name "unconnected-(U7-PE10-Pad63)") (class "Default")
      (node (ref "U7") (pin "63") (pinfunction "PE10_63") (pintype "passive"))
    )
    (net (code "97") (name "unconnected-(U7-PE11-Pad64)") (class "Default")
      (node (ref "U7") (pin "64") (pinfunction "PE11_64") (pintype "passive"))
    )
    (net (code "98") (name "unconnected-(U7-PE12-Pad65)") (class "Default")
      (node (ref "U7") (pin "65") (pinfunction "PE12_65") (pintype "passive"))
    )
    (net (code "99") (name "unconnected-(U7-PE13-Pad66)") (class "Default")
      (node (ref "U7") (pin "66") (pinfunction "PE13_66") (pintype "passive"))
    )
    (net (code "100") (name "unconnected-(U7-PE14-Pad67)") (class "Default")
      (node (ref "U7") (pin "67") (pinfunction "PE14_67") (pintype "passive"))
    )
    (net (code "101") (name "unconnected-(U7-PE15-Pad68)") (class "Default")
      (node (ref "U7") (pin "68") (pinfunction "PE15_68") (pintype "passive"))
    )
    (net (code "102") (name "unconnected-(U7-PF0-Pad10)") (class "Default")
      (node (ref "U7") (pin "10") (pinfunction "PF0_10") (pintype "passive"))
    )
    (net (code "103") (name "unconnected-(U7-PF1-Pad11)") (class "Default")
      (node (ref "U7") (pin "11") (pinfunction "PF1_11") (pintype "passive"))
    )
    (net (code "104") (name "unconnected-(U7-PF2-Pad12)") (class "Default")
      (node (ref "U7") (pin "12") (pinfunction "PF2_12") (pintype "passive"))
    )
    (net (code "105") (name "unconnected-(U7-PF3-Pad13)") (class "Default")
      (node (ref "U7") (pin "13") (pinfunction "PF3_13") (pintype "passive"))
    )
    (net (code "106") (name "unconnected-(U7-PF4-Pad14)") (class "Default")
      (node (ref "U7") (pin "14") (pinfunction "PF4_14") (pintype "passive"))
    )
    (net (code "107") (name "unconnected-(U7-PF5-Pad15)") (class "Default")
      (node (ref "U7") (pin "15") (pinfunction "PF5_15") (pintype "passive"))
    )
    (net (code "108") (name "unconnected-(U7-PF6-Pad18)") (class "Default")
      (node (ref "U7") (pin "18") (pinfunction "PF6_18") (pintype "passive"))
    )
    (net (code "109") (name "unconnected-(U7-PF7-Pad19)") (class "Default")
      (node (ref "U7") (pin "19") (pinfunction "PF7_19") (pintype "passive"))
    )
    (net (code "110") (name "unconnected-(U7-PF8-Pad20)") (class "Default")
      (node (ref "U7") (pin "20") (pinfunction "PF8_20") (pintype "passive"))
    )
    (net (code "111") (name "unconnected-(U7-PF9-Pad21)") (class "Default")
      (node (ref "U7") (pin "21") (pinfunction "PF9_21") (pintype "passive"))
    )
    (net (code "112") (name "unconnected-(U7-PF10-Pad22)") (class "Default")
      (node (ref "U7") (pin "22") (pinfunction "PF10_22") (pintype "passive"))
    )
    (net (code "113") (name "unconnected-(U7-PF11-Pad49)") (class "Default")
      (node (ref "U7") (pin "49") (pinfunction "PF11_49") (pintype "passive"))
    )
    (net (code "114") (name "unconnected-(U7-PF12-Pad50)") (class "Default")
      (node (ref "U7") (pin "50") (pinfunction "PF12_50") (pintype "passive"))
    )
    (net (code "115") (name "unconnected-(U7-PF13-Pad53)") (class "Default")
      (node (ref "U7") (pin "53") (pinfunction "PF13_53") (pintype "passive"))
    )
    (net (code "116") (name "unconnected-(U7-PF14-Pad54)") (class "Default")
      (node (ref "U7") (pin "54") (pinfunction "PF14_54") (pintype "passive"))
    )
    (net (code "117") (name "unconnected-(U7-PF15-Pad55)") (class "Default")
      (node (ref "U7") (pin "55") (pinfunction "PF15_55") (pintype "passive"))
    )
    (net (code "118") (name "unconnected-(U7-PG0-Pad56)") (class "Default")
      (node (ref "U7") (pin "56") (pinfunction "PG0_56") (pintype "passive"))
    )
    (net (code "119") (name "unconnected-(U7-PG1-Pad57)") (class "Default")
      (node (ref "U7") (pin "57") (pinfunction "PG1_57") (pintype "passive"))
    )
    (net (code "120") (name "unconnected-(U7-PG9-Pad124)") (class "Default")
      (node (ref "U7") (pin "124") (pinfunction "PG9_124") (pintype "passive"))
    )
    (net (code "121") (name "unconnected-(U7-PG10-Pad125)") (class "Default")
      (node (ref "U7") (pin "125") (pinfunction "PG10_125") (pintype "passive"))
    )
    (net (code "122") (name "unconnected-(U7-PG11-Pad126)") (class "Default")
      (node (ref "U7") (pin "126") (pinfunction "PG11_126") (pintype "passive"))
    )
    (net (code "123") (name "unconnected-(U7-PG12-Pad127)") (class "Default")
      (node (ref "U7") (pin "127") (pinfunction "PG12_127") (pintype "passive"))
    )
    (net (code "124") (name "unconnected-(U7-PG13-Pad128)") (class "Default")
      (node (ref "U7") (pin "128") (pinfunction "PG13_128") (pintype "passive"))
    )
    (net (code "125") (name "unconnected-(U7-PG14-Pad129)") (class "Default")
      (node (ref "U7") (pin "129") (pinfunction "PG14_129") (pintype "passive"))
    )
    (net (code "126") (name "unconnected-(U7-PG15-Pad132)") (class "Default")
      (node (ref "U7") (pin "132") (pinfunction "PG15_132") (pintype "passive"))
    )
  )
)
